# Isolated_Power.net
KiCad netlist of a schematic drawn in Altium Designer
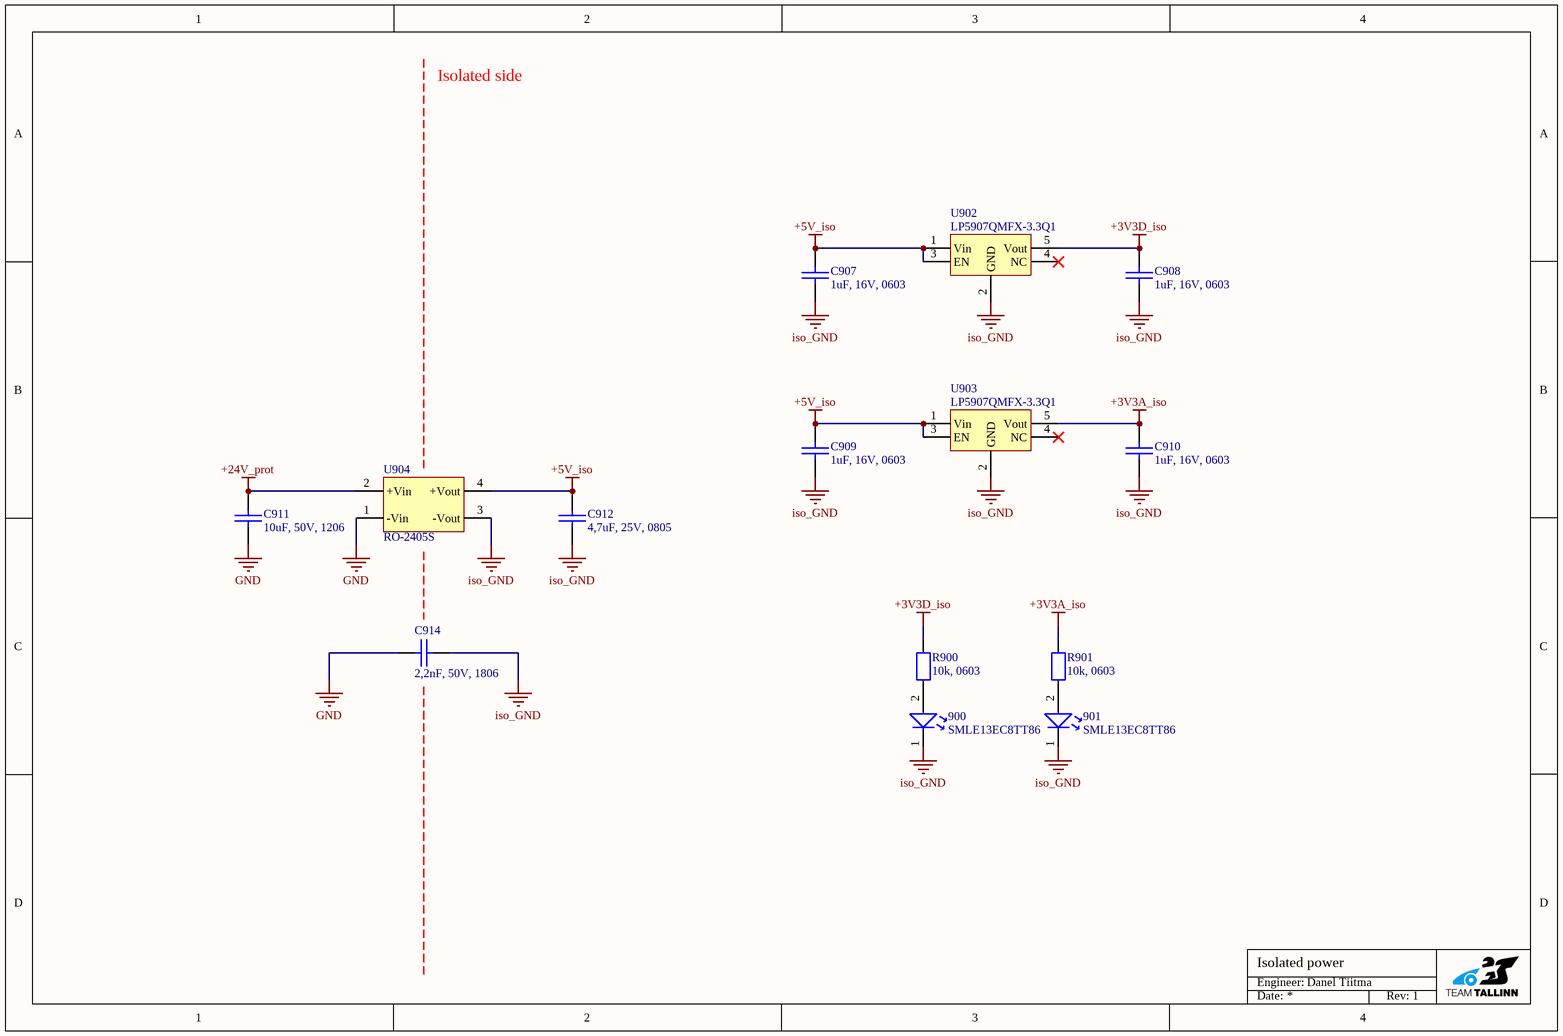
[diagram p0: Isolated_Power.SchDoc]

(export (version "E")
  (design (tool "Eeschema 10.0.6"))
  (components
    (comp (ref "900")
      (value "SMLE13EC8TT86")
      (footprint "LED [0603] 1608")
      (description "Single Color LED, Green, Colorless Transparent, 1.2mm")
      (libsource (lib "Formula Student Team Tallinn (Estonia)") (part "Diode LED"))
    )
    (comp (ref "901")
      (value "SMLE13EC8TT86")
      (footprint "LED [0603] 1608")
      (description "Single Color LED, Green, Colorless Transparent, 1.2mm")
      (libsource (lib "Formula Student Team Tallinn (Estonia)") (part "Diode LED"))
    )
    (comp (ref "C907")
      (value "1uF, 16V, 0603")
      (footprint "CAP [0603] 1608")
      (description "Default capacitor part")
      (libsource (lib "Formula Student Team Tallinn (Estonia)") (part "Capacitor"))
    )
    (comp (ref "C908")
      (value "1uF, 16V, 0603")
      (footprint "CAP [0603] 1608")
      (description "Default capacitor part")
      (libsource (lib "Formula Student Team Tallinn (Estonia)") (part "Capacitor"))
    )
    (comp (ref "C909")
      (value "1uF, 16V, 0603")
      (footprint "CAP [0603] 1608")
      (description "Default capacitor part")
      (libsource (lib "Formula Student Team Tallinn (Estonia)") (part "Capacitor"))
    )
    (comp (ref "C910")
      (value "1uF, 16V, 0603")
      (footprint "CAP [0603] 1608")
      (description "Default capacitor part")
      (libsource (lib "Formula Student Team Tallinn (Estonia)") (part "Capacitor"))
    )
    (comp (ref "C911")
      (value "10uF, 50V, 1206")
      (footprint "CAP [1206] 3216")
      (description "Default capacitor part")
      (libsource (lib "Formula Student Team Tallinn (Estonia)") (part "Capacitor"))
    )
    (comp (ref "C912")
      (value "4,7uF, 25V, 0805")
      (footprint "CAP [0805] 2012")
      (description "Default capacitor part")
      (libsource (lib "Formula Student Team Tallinn (Estonia)") (part "Capacitor"))
    )
    (comp (ref "C914")
      (value "2,2nF, 50V, 1806")
      (footprint "CAP [1806] 4516")
      (description "Default capacitor part")
      (libsource (lib "Formula Student Team Tallinn (Estonia)") (part "Capacitor"))
    )
    (comp (ref "R900")
      (value "10k, 0603")
      (footprint "RES [0603] 1608")
      (description "Standard resistor part")
      (libsource (lib "Formula Student Team Tallinn (Estonia)") (part "Resistor"))
    )
    (comp (ref "R901")
      (value "10k, 0603")
      (footprint "RES [0603] 1608")
      (description "Standard resistor part")
      (libsource (lib "Formula Student Team Tallinn (Estonia)") (part "Resistor"))
    )
    (comp (ref "U902")
      (value "LP5907QMFX-3.3Q1")
      (footprint "SOT23-5")
      (description "Fixed Positive LDO Regulator, 3.3V, 0.25V Dropout, PDSO5")
      (fields (field (name "MANUFACTURER") "Texas Instruments"))
      (libsource (lib "Formula Student Team Tallinn (Estonia)") (part "LDO 5-pin"))
    )
    (comp (ref "U903")
      (value "LP5907QMFX-3.3Q1")
      (footprint "SOT23-5")
      (description "Fixed Positive LDO Regulator, 3.3V, 0.25V Dropout, PDSO5")
      (fields (field (name "MANUFACTURER") "Texas Instruments"))
      (libsource (lib "Formula Student Team Tallinn (Estonia)") (part "LDO 5-pin"))
    )
    (comp (ref "U904")
      (value "RO-2405S")
      (footprint "SIP-4")
      (description "DC-DC Unregulated Power Supply Module, 1 Output, 1W, Hybrid")
      (fields (field (name "MANUFACTURER") "Recom Power"))
      (libsource (lib "Formula Student Team Tallinn (Estonia)") (part "SIP-4"))
    )
  )
  (nets
    (net (code "1") (name "+3V3A_iso") (class "Default")
      (node (ref "C910") (pin "2") (pinfunction "2_2") (pintype "passive"))
      (node (ref "R901") (pin "2") (pinfunction "2_2") (pintype "passive"))
      (node (ref "U903") (pin "5") (pinfunction "Vout_5") (pintype "passive"))
    )
    (net (code "2") (name "+3V3D_iso") (class "Default")
      (node (ref "C908") (pin "2") (pinfunction "2_2") (pintype "passive"))
      (node (ref "R900") (pin "2") (pinfunction "2_2") (pintype "passive"))
      (node (ref "U902") (pin "5") (pinfunction "Vout_5") (pintype "passive"))
    )
    (net (code "3") (name "+5V_iso") (class "Default")
      (node (ref "C907") (pin "2") (pinfunction "2_2") (pintype "passive"))
      (node (ref "C909") (pin "2") (pinfunction "2_2") (pintype "passive"))
      (node (ref "C912") (pin "2") (pinfunction "2_2") (pintype "passive"))
      (node (ref "U902") (pin "1") (pinfunction "Vin_1") (pintype "passive"))
      (node (ref "U902") (pin "3") (pinfunction "EN_3") (pintype "passive"))
      (node (ref "U903") (pin "1") (pinfunction "Vin_1") (pintype "passive"))
      (node (ref "U903") (pin "3") (pinfunction "EN_3") (pintype "passive"))
      (node (ref "U904") (pin "4") (pinfunction "+Vout_4") (pintype "passive"))
    )
    (net (code "4") (name "+24V_prot") (class "Default")
      (node (ref "C911") (pin "2") (pinfunction "2_2") (pintype "passive"))
      (node (ref "U904") (pin "2") (pinfunction "+Vin_2") (pintype "passive"))
    )
    (net (code "5") (name "GND") (class "Default")
      (node (ref "C911") (pin "1") (pinfunction "1_1") (pintype "passive"))
      (node (ref "C914") (pin "1") (pinfunction "1_1") (pintype "passive"))
      (node (ref "U904") (pin "1") (pinfunction "-Vin_1") (pintype "passive"))
    )
    (net (code "6") (name "Net-(900-Pad2)") (class "Default")
      (node (ref "900") (pin "2") (pinfunction "2_2") (pintype "passive"))
      (node (ref "R900") (pin "1") (pinfunction "1_1") (pintype "passive"))
    )
    (net (code "7") (name "Net-(901-Pad2)") (class "Default")
      (node (ref "901") (pin "2") (pinfunction "2_2") (pintype "passive"))
      (node (ref "R901") (pin "1") (pinfunction "1_1") (pintype "passive"))
    )
    (net (code "8") (name "iso_GND") (class "Default")
      (node (ref "900") (pin "1") (pinfunction "1_1") (pintype "passive"))
      (node (ref "901") (pin "1") (pinfunction "1_1") (pintype "passive"))
      (node (ref "C907") (pin "1") (pinfunction "1_1") (pintype "passive"))
      (node (ref "C908") (pin "1") (pinfunction "1_1") (pintype "passive"))
      (node (ref "C909") (pin "1") (pinfunction "1_1") (pintype "passive"))
      (node (ref "C910") (pin "1") (pinfunction "1_1") (pintype "passive"))
      (node (ref "C912") (pin "1") (pinfunction "1_1") (pintype "passive"))
      (node (ref "C914") (pin "2") (pinfunction "2_2") (pintype "passive"))
      (node (ref "U902") (pin "2") (pinfunction "GND_2") (pintype "passive"))
      (node (ref "U903") (pin "2") (pinfunction "GND_2") (pintype "passive"))
      (node (ref "U904") (pin "3") (pinfunction "-Vout_3") (pintype "passive"))
    )
    (net (code "9") (name "unconnected-(U902-NC-Pad4)") (class "Default")
      (node (ref "U902") (pin "4") (pinfunction "NC_4") (pintype "passive+no_connect"))
    )
    (net (code "10") (name "unconnected-(U903-NC-Pad4)") (class "Default")
      (node (ref "U903") (pin "4") (pinfunction "NC_4") (pintype "passive+no_connect"))
    )
  )
)
